# Wireless_FanCoil_Controller_Atmega_v2_2.net
KiCad netlist of a schematic drawn in EAGLE
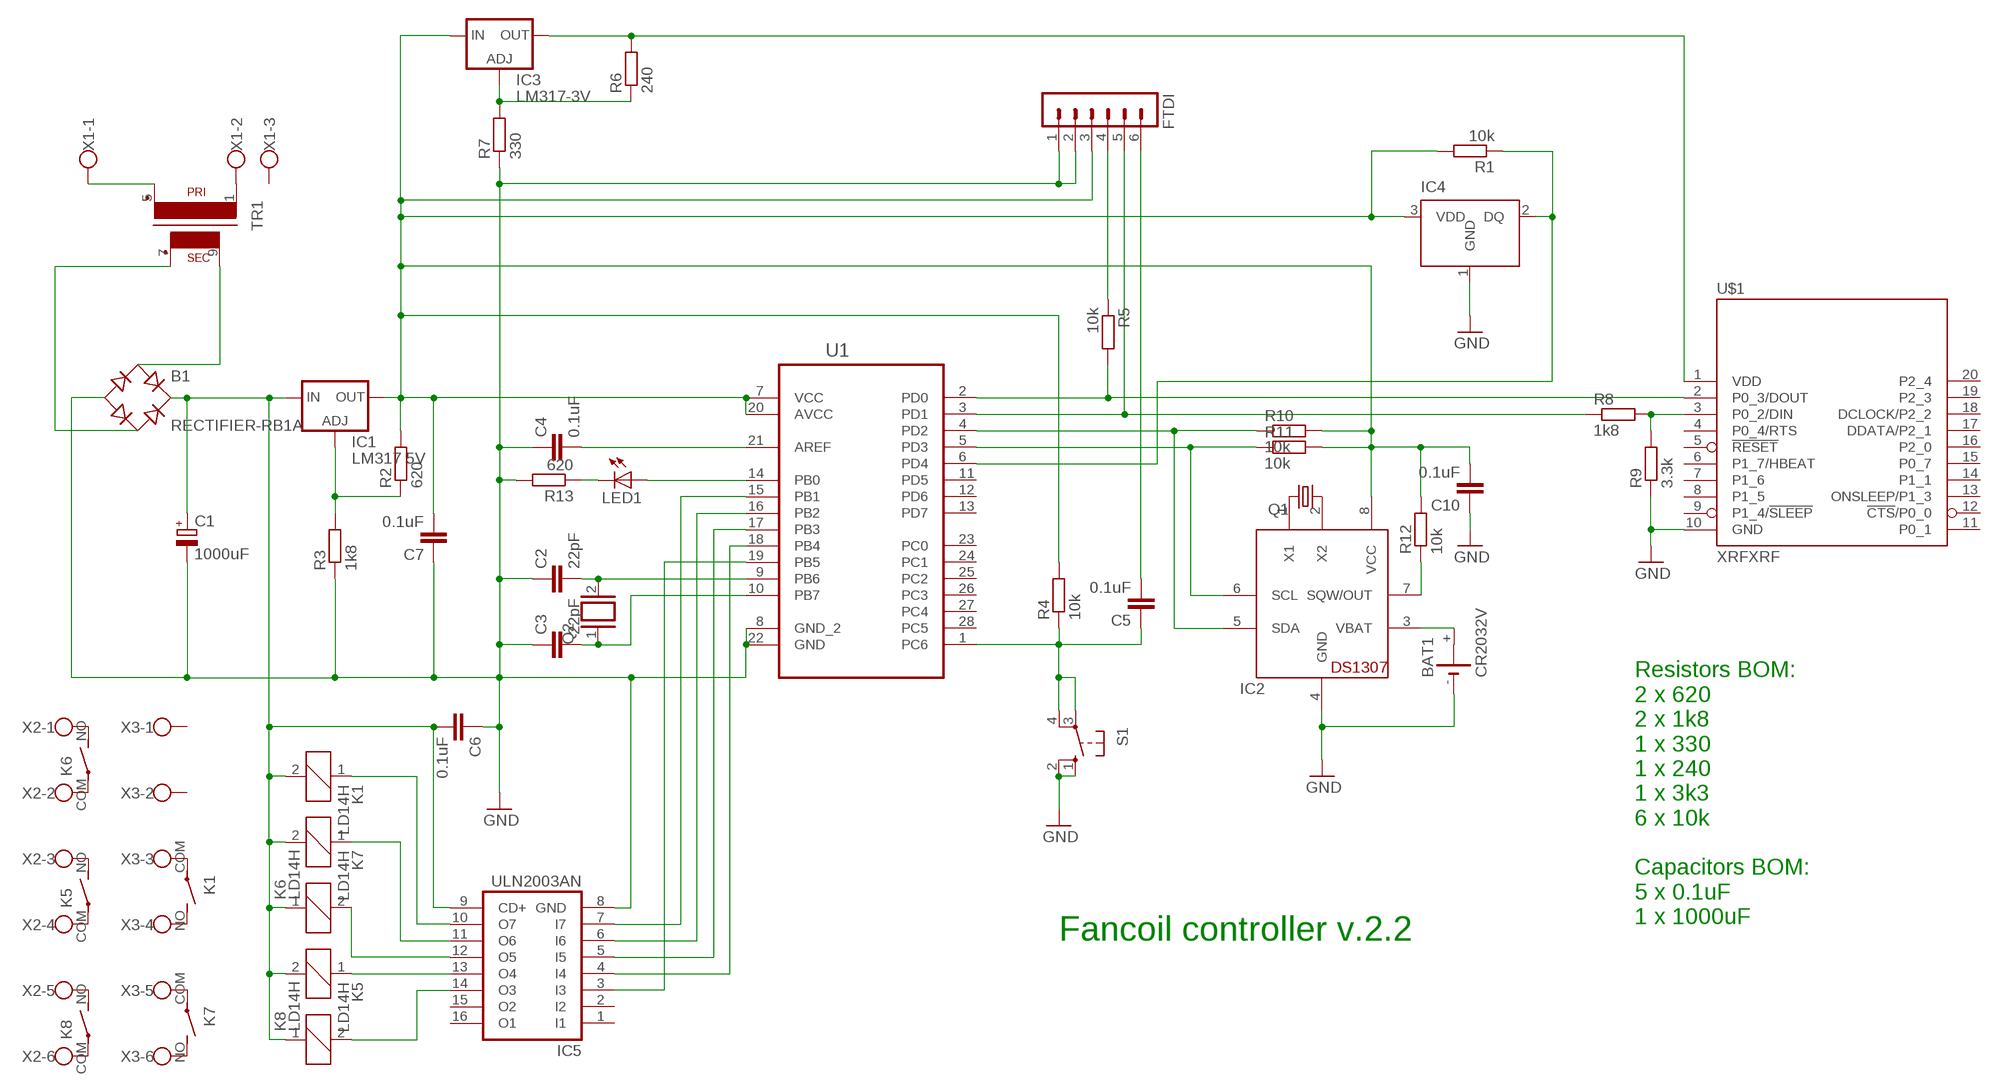
[diagram p0: schematic, sheet 1]

(export (version "E")
  (design (tool "Eeschema 10.0.6"))
  (components
    (comp (ref "B1")
      (value "RECTIFIER-RB1A")
      (footprint "eagle-import:RB1A")
      (libsource (lib "eagle-import") (part "RECTIFIER-RB1A"))
    )
    (comp (ref "BAT1")
      (value "CR2032V")
      (footprint "eagle-import:CR2032V")
      (libsource (lib "eagle-import") (part "CR2032V"))
    )
    (comp (ref "C1")
      (value "1000uF")
      (footprint "eagle-import:E5-10,5")
      (libsource (lib "eagle-import") (part "CPOL-EUE5-10.5"))
    )
    (comp (ref "C2")
      (value "22pF")
      (footprint "eagle-import:C025-025X050")
      (libsource (lib "eagle-import") (part "C-EU025-025X050"))
    )
    (comp (ref "C3")
      (value "22pF")
      (footprint "eagle-import:C025-025X050")
      (libsource (lib "eagle-import") (part "C-EU025-025X050"))
    )
    (comp (ref "C4")
      (value "0.1uF")
      (footprint "eagle-import:C050-025X075")
      (libsource (lib "eagle-import") (part "C-EU050-025X075"))
    )
    (comp (ref "C5")
      (value "0.1uF")
      (footprint "eagle-import:C050-025X075")
      (libsource (lib "eagle-import") (part "C-EU050-025X075"))
    )
    (comp (ref "C6")
      (value "0.1uF")
      (footprint "eagle-import:C050-025X075")
      (libsource (lib "eagle-import") (part "C-EU050-025X075"))
    )
    (comp (ref "C7")
      (value "0.1uF")
      (footprint "eagle-import:C050-025X075")
      (libsource (lib "eagle-import") (part "C-EU050-025X075"))
    )
    (comp (ref "C10")
      (value "0.1uF")
      (footprint "eagle-import:C050-025X075")
      (libsource (lib "eagle-import") (part "C-EU050-025X075"))
    )
    (comp (ref "FTDI")
      (value "MA06-1")
      (footprint "eagle-import:MA06-1")
      (libsource (lib "eagle-import") (part "MA06-1"))
    )
    (comp (ref "IC1")
      (value "LM317 5V")
      (footprint "eagle-import:317TS")
      (libsource (lib "eagle-import") (part "LM317TS"))
    )
    (comp (ref "IC2")
      (value "DS1307")
      (footprint "eagle-import:DIL08")
      (libsource (lib "eagle-import") (part "DS1307"))
    )
    (comp (ref "IC3")
      (value "LM317-3V")
      (footprint "eagle-import:317TS")
      (libsource (lib "eagle-import") (part "LM317TS"))
    )
    (comp (ref "IC4")
      (value "DS1820")
      (footprint "eagle-import:TO-92")
      (libsource (lib "eagle-import") (part "DS1820"))
    )
    (comp (ref "IC5")
      (value "ULN2003AN")
      (footprint "eagle-import:DIL16")
      (libsource (lib "eagle-import") (part "ULN2003AN"))
    )
    (comp (ref "K1")
      (value "LD14H")
      (footprint "eagle-import:LD")
      (fields
        (field (name "MF") "FARNELL")
        (field (name "MPN") "ALD112")
        (field (name "OC_FARNELL") "3727166")
        (field (name "OC_NEWARK") "70C6003")
      )
      (libsource (lib "eagle-import") (part "LD?14H"))
    )
    (comp (ref "K5")
      (value "LD14H")
      (footprint "eagle-import:LD")
      (fields
        (field (name "MF") "FARNELL")
        (field (name "MPN") "ALD112")
        (field (name "OC_FARNELL") "3727166")
        (field (name "OC_NEWARK") "70C6003")
      )
      (libsource (lib "eagle-import") (part "LD?14H"))
    )
    (comp (ref "K6")
      (value "LD14H")
      (footprint "eagle-import:LD")
      (fields
        (field (name "MF") "FARNELL")
        (field (name "MPN") "ALD112")
        (field (name "OC_FARNELL") "3727166")
        (field (name "OC_NEWARK") "70C6003")
      )
      (libsource (lib "eagle-import") (part "LD?14H"))
    )
    (comp (ref "K7")
      (value "LD14H")
      (footprint "eagle-import:LD")
      (fields
        (field (name "MF") "FARNELL")
        (field (name "MPN") "ALD112")
        (field (name "OC_FARNELL") "3727166")
        (field (name "OC_NEWARK") "70C6003")
      )
      (libsource (lib "eagle-import") (part "LD?14H"))
    )
    (comp (ref "K8")
      (value "LD14H")
      (footprint "eagle-import:LD")
      (fields
        (field (name "MF") "FARNELL")
        (field (name "MPN") "ALD112")
        (field (name "OC_FARNELL") "3727166")
        (field (name "OC_NEWARK") "70C6003")
      )
      (libsource (lib "eagle-import") (part "LD?14H"))
    )
    (comp (ref "LED1")
      (value "LED3MM")
      (footprint "eagle-import:LED3MM")
      (libsource (lib "eagle-import") (part "LED3MM"))
    )
    (comp (ref "Q1")
      (value "CRYSTALTC26H")
      (footprint "eagle-import:TC26H")
      (libsource (lib "eagle-import") (part "CRYSTALTC26H"))
    )
    (comp (ref "Q2")
      (value "XTAL/S")
      (footprint "eagle-import:QS")
      (libsource (lib "eagle-import") (part "XTAL/S"))
    )
    (comp (ref "R1")
      (value "10k")
      (footprint "eagle-import:0207_5V")
      (libsource (lib "eagle-import") (part "R-EU_0207/5V"))
    )
    (comp (ref "R2")
      (value "620")
      (footprint "eagle-import:0207_5V")
      (libsource (lib "eagle-import") (part "R-EU_0207/5V"))
    )
    (comp (ref "R3")
      (value "1k8")
      (footprint "eagle-import:0207_5V")
      (libsource (lib "eagle-import") (part "R-EU_0207/5V"))
    )
    (comp (ref "R4")
      (value "10k")
      (footprint "eagle-import:0207_5V")
      (libsource (lib "eagle-import") (part "R-EU_0207/5V"))
    )
    (comp (ref "R5")
      (value "10k")
      (footprint "eagle-import:0207_5V")
      (libsource (lib "eagle-import") (part "R-EU_0207/5V"))
    )
    (comp (ref "R6")
      (value "240")
      (footprint "eagle-import:0207_5V")
      (libsource (lib "eagle-import") (part "R-EU_0207/5V"))
    )
    (comp (ref "R7")
      (value "330")
      (footprint "eagle-import:0207_5V")
      (libsource (lib "eagle-import") (part "R-EU_0207/5V"))
    )
    (comp (ref "R8")
      (value "1k8")
      (footprint "eagle-import:0207_12")
      (libsource (lib "eagle-import") (part "R-EU_0207/12"))
    )
    (comp (ref "R9")
      (value "3.3k")
      (footprint "eagle-import:0207_5V")
      (libsource (lib "eagle-import") (part "R-EU_0207/5V"))
    )
    (comp (ref "R10")
      (value "10k")
      (footprint "eagle-import:0207_5V")
      (libsource (lib "eagle-import") (part "R-EU_0207/5V"))
    )
    (comp (ref "R11")
      (value "10k")
      (footprint "eagle-import:0207_5V")
      (libsource (lib "eagle-import") (part "R-EU_0207/5V"))
    )
    (comp (ref "R12")
      (value "10k")
      (footprint "eagle-import:0207_5V")
      (libsource (lib "eagle-import") (part "R-EU_0207/5V"))
    )
    (comp (ref "R13")
      (value "620")
      (footprint "eagle-import:0207_5V")
      (libsource (lib "eagle-import") (part "R-EU_0207/5V"))
    )
    (comp (ref "S1")
      (value "10-XX")
      (footprint "eagle-import:B3F-10XX")
      (fields (field (name "MPN") "B3F-1000"))
      (libsource (lib "eagle-import") (part "10-XX"))
    )
    (comp (ref "TR1")
      (value "EI30-1")
      (footprint "eagle-import:EI30-1")
      (libsource (lib "eagle-import") (part "EI30-1"))
    )
    (comp (ref "U$1")
      (value "XRFXRF")
      (footprint "eagle-import:XRF")
      (libsource (lib "eagle-import") (part "XRFXRF"))
    )
    (comp (ref "U1")
      (value "ATMEGA328P-PU")
      (footprint "eagle-import:DIP254P762X457-28")
      (libsource (lib "eagle-import") (part "ATMEGA328P-PU"))
    )
    (comp (ref "X1")
      (value "W237-103")
      (footprint "eagle-import:W237-103")
      (fields (field (name "MPN") "237-103"))
      (libsource (lib "eagle-import") (part "W237-103"))
    )
    (comp (ref "X2")
      (value "W237-136")
      (footprint "eagle-import:W237-136")
      (fields (field (name "MPN") "237-136"))
      (libsource (lib "eagle-import") (part "W237-136"))
    )
    (comp (ref "X3")
      (value "W237-136")
      (footprint "eagle-import:W237-136")
      (fields (field (name "MPN") "237-136"))
      (libsource (lib "eagle-import") (part "W237-136"))
    )
  )
  (nets
    (net (code "1") (name "GND") (class "Default")
      (node (ref "B1") (pin "-") (pinfunction "-_-") (pintype "passive"))
      (node (ref "BAT1") (pin "-") (pinfunction "-_-") (pintype "passive"))
      (node (ref "C1") (pin "-") (pinfunction "-_-") (pintype "passive"))
      (node (ref "C10") (pin "1") (pinfunction "1_1") (pintype "passive"))
      (node (ref "C2") (pin "1") (pinfunction "1_1") (pintype "passive"))
      (node (ref "C3") (pin "1") (pinfunction "1_1") (pintype "passive"))
      (node (ref "C4") (pin "1") (pinfunction "1_1") (pintype "passive"))
      (node (ref "C6") (pin "1") (pinfunction "1_1") (pintype "passive"))
      (node (ref "C7") (pin "1") (pinfunction "1_1") (pintype "passive"))
      (node (ref "FTDI") (pin "1") (pinfunction "1_1") (pintype "passive"))
      (node (ref "FTDI") (pin "2") (pinfunction "2_2") (pintype "passive"))
      (node (ref "IC2") (pin "4") (pinfunction "GND_4") (pintype "power_in"))
      (node (ref "IC4") (pin "1") (pinfunction "GND_1") (pintype "power_in"))
      (node (ref "IC5") (pin "8") (pinfunction "GND_8") (pintype "power_in"))
      (node (ref "R13") (pin "2") (pinfunction "2_2") (pintype "passive"))
      (node (ref "R3") (pin "1") (pinfunction "1_1") (pintype "passive"))
      (node (ref "R7") (pin "1") (pinfunction "1_1") (pintype "passive"))
      (node (ref "R9") (pin "1") (pinfunction "1_1") (pintype "passive"))
      (node (ref "S1") (pin "1") (pinfunction "S_1") (pintype "passive"))
      (node (ref "S1") (pin "2") (pinfunction "S1_2") (pintype "passive"))
      (node (ref "U$1") (pin "10") (pinfunction "GND_10") (pintype "power_in"))
      (node (ref "U1") (pin "22") (pinfunction "GND_22") (pintype "passive"))
      (node (ref "U1") (pin "8") (pinfunction "GND_2_8") (pintype "passive"))
    )
    (net (code "2") (name "Net-(C5-Pad2)") (class "Default")
      (node (ref "C5") (pin "2") (pinfunction "2_2") (pintype "passive"))
      (node (ref "FTDI") (pin "6") (pinfunction "6_6") (pintype "passive"))
    )
    (net (code "3") (name "Net-(FTDI-Pad4)") (class "Default")
      (node (ref "FTDI") (pin "4") (pinfunction "4_4") (pintype "passive"))
      (node (ref "R5") (pin "1") (pinfunction "1_1") (pintype "passive"))
    )
    (net (code "4") (name "Net-(IC1-ADJ)") (class "Default")
      (node (ref "IC1") (pin "1") (pinfunction "ADJ_1") (pintype "input"))
      (node (ref "R2") (pin "1") (pinfunction "1_1") (pintype "passive"))
      (node (ref "R3") (pin "2") (pinfunction "2_2") (pintype "passive"))
    )
    (net (code "5") (name "Net-(IC1-IN)") (class "Default")
      (node (ref "B1") (pin "+") (pinfunction "+_+") (pintype "passive"))
      (node (ref "C1") (pin "+") (pinfunction "+_+") (pintype "passive"))
      (node (ref "C6") (pin "2") (pinfunction "2_2") (pintype "passive"))
      (node (ref "IC1") (pin "3") (pinfunction "IN_3") (pintype "input"))
      (node (ref "IC5") (pin "9") (pinfunction "CD+_9") (pintype "passive"))
      (node (ref "K1") (pin "2") (pinfunction "2_2") (pintype "passive"))
      (node (ref "K5") (pin "2") (pinfunction "2_2") (pintype "passive"))
      (node (ref "K6") (pin "1") (pinfunction "1_1") (pintype "passive"))
      (node (ref "K7") (pin "2") (pinfunction "2_2") (pintype "passive"))
      (node (ref "K8") (pin "1") (pinfunction "1_1") (pintype "passive"))
    )
    (net (code "6") (name "Net-(IC1-OUT)") (class "Default")
      (node (ref "C10") (pin "2") (pinfunction "2_2") (pintype "passive"))
      (node (ref "C7") (pin "2") (pinfunction "2_2") (pintype "passive"))
      (node (ref "FTDI") (pin "3") (pinfunction "3_3") (pintype "passive"))
      (node (ref "IC1") (pin "2") (pinfunction "OUT_2") (pintype "passive"))
      (node (ref "IC2") (pin "8") (pinfunction "VCC_8") (pintype "power_in"))
      (node (ref "IC3") (pin "3") (pinfunction "IN_3") (pintype "input"))
      (node (ref "IC4") (pin "3") (pinfunction "VDD_3") (pintype "input"))
      (node (ref "R1") (pin "2") (pinfunction "2_2") (pintype "passive"))
      (node (ref "R10") (pin "2") (pinfunction "2_2") (pintype "passive"))
      (node (ref "R11") (pin "2") (pinfunction "2_2") (pintype "passive"))
      (node (ref "R12") (pin "2") (pinfunction "2_2") (pintype "passive"))
      (node (ref "R2") (pin "2") (pinfunction "2_2") (pintype "passive"))
      (node (ref "R4") (pin "2") (pinfunction "2_2") (pintype "passive"))
      (node (ref "U1") (pin "20") (pinfunction "AVCC_20") (pintype "power_in"))
      (node (ref "U1") (pin "7") (pinfunction "VCC_7") (pintype "power_in"))
    )
    (net (code "7") (name "Net-(IC2-SCL)") (class "Default")
      (node (ref "IC2") (pin "6") (pinfunction "SCL_6") (pintype "bidirectional"))
      (node (ref "R11") (pin "1") (pinfunction "1_1") (pintype "passive"))
      (node (ref "U1") (pin "5") (pinfunction "PD3_5") (pintype "bidirectional"))
    )
    (net (code "8") (name "Net-(IC2-SDA)") (class "Default")
      (node (ref "IC2") (pin "5") (pinfunction "SDA_5") (pintype "bidirectional"))
      (node (ref "R10") (pin "1") (pinfunction "1_1") (pintype "passive"))
      (node (ref "U1") (pin "4") (pinfunction "PD2_4") (pintype "bidirectional"))
    )
    (net (code "9") (name "Net-(IC2-SQW{slash}OUT)") (class "Default")
      (node (ref "IC2") (pin "7") (pinfunction "SQW/OUT_7") (pintype "bidirectional"))
      (node (ref "R12") (pin "1") (pinfunction "1_1") (pintype "passive"))
    )
    (net (code "10") (name "Net-(IC2-VBAT)") (class "Default")
      (node (ref "BAT1") (pin "+") (pinfunction "+_+") (pintype "passive"))
      (node (ref "IC2") (pin "3") (pinfunction "VBAT_3") (pintype "power_in"))
    )
    (net (code "11") (name "Net-(IC2-X1)") (class "Default")
      (node (ref "IC2") (pin "1") (pinfunction "X1_1") (pintype "passive"))
      (node (ref "Q1") (pin "2") (pinfunction "2_2") (pintype "passive"))
    )
    (net (code "12") (name "Net-(IC2-X2)") (class "Default")
      (node (ref "IC2") (pin "2") (pinfunction "X2_2") (pintype "passive"))
      (node (ref "Q1") (pin "1") (pinfunction "1_1") (pintype "passive"))
    )
    (net (code "13") (name "Net-(IC3-ADJ)") (class "Default")
      (node (ref "IC3") (pin "1") (pinfunction "ADJ_1") (pintype "input"))
      (node (ref "R6") (pin "1") (pinfunction "1_1") (pintype "passive"))
      (node (ref "R7") (pin "2") (pinfunction "2_2") (pintype "passive"))
    )
    (net (code "14") (name "Net-(IC3-OUT)") (class "Default")
      (node (ref "IC3") (pin "2") (pinfunction "OUT_2") (pintype "passive"))
      (node (ref "R6") (pin "2") (pinfunction "2_2") (pintype "passive"))
      (node (ref "U$1") (pin "1") (pinfunction "VDD_1") (pintype "power_in"))
    )
    (net (code "15") (name "Net-(IC4-DQ)") (class "Default")
      (node (ref "IC4") (pin "2") (pinfunction "DQ_2") (pintype "output"))
      (node (ref "R1") (pin "1") (pinfunction "1_1") (pintype "passive"))
      (node (ref "U1") (pin "6") (pinfunction "PD4_6") (pintype "bidirectional"))
    )
    (net (code "16") (name "Net-(IC5-I3)") (class "Default")
      (node (ref "IC5") (pin "3") (pinfunction "I3_3") (pintype "input"))
      (node (ref "U1") (pin "19") (pinfunction "PB5_19") (pintype "bidirectional"))
    )
    (net (code "17") (name "Net-(IC5-I4)") (class "Default")
      (node (ref "IC5") (pin "4") (pinfunction "I4_4") (pintype "input"))
      (node (ref "U1") (pin "18") (pinfunction "PB4_18") (pintype "bidirectional"))
    )
    (net (code "18") (name "Net-(IC5-I5)") (class "Default")
      (node (ref "IC5") (pin "5") (pinfunction "I5_5") (pintype "input"))
      (node (ref "U1") (pin "17") (pinfunction "PB3_17") (pintype "bidirectional"))
    )
    (net (code "19") (name "Net-(IC5-I6)") (class "Default")
      (node (ref "IC5") (pin "6") (pinfunction "I6_6") (pintype "input"))
      (node (ref "U1") (pin "16") (pinfunction "PB2_16") (pintype "bidirectional"))
    )
    (net (code "20") (name "Net-(IC5-I7)") (class "Default")
      (node (ref "IC5") (pin "7") (pinfunction "I7_7") (pintype "input"))
      (node (ref "U1") (pin "15") (pinfunction "PB1_15") (pintype "bidirectional"))
    )
    (net (code "21") (name "Net-(IC5-O3)") (class "Default")
      (node (ref "IC5") (pin "14") (pinfunction "O3_14") (pintype "open_collector"))
      (node (ref "K8") (pin "2") (pinfunction "2_2") (pintype "passive"))
    )
    (net (code "22") (name "Net-(IC5-O4)") (class "Default")
      (node (ref "IC5") (pin "13") (pinfunction "O4_13") (pintype "open_collector"))
      (node (ref "K5") (pin "1") (pinfunction "1_1") (pintype "passive"))
    )
    (net (code "23") (name "Net-(IC5-O5)") (class "Default")
      (node (ref "IC5") (pin "12") (pinfunction "O5_12") (pintype "open_collector"))
      (node (ref "K6") (pin "2") (pinfunction "2_2") (pintype "passive"))
    )
    (net (code "24") (name "Net-(IC5-O6)") (class "Default")
      (node (ref "IC5") (pin "11") (pinfunction "O6_11") (pintype "open_collector"))
      (node (ref "K7") (pin "1") (pinfunction "1_1") (pintype "passive"))
    )
    (net (code "25") (name "Net-(IC5-O7)") (class "Default")
      (node (ref "IC5") (pin "10") (pinfunction "O7_10") (pintype "open_collector"))
      (node (ref "K1") (pin "1") (pinfunction "1_1") (pintype "passive"))
    )
    (net (code "26") (name "Net-(K1B-P)") (class "Default")
      (node (ref "K1") (pin "COM") (pinfunction "P_COM") (pintype "passive"))
      (node (ref "X3") (pin "3") (pinfunction "KL_3") (pintype "passive"))
    )
    (net (code "27") (name "Net-(K1B-S)") (class "Default")
      (node (ref "K1") (pin "NO") (pinfunction "S_NO") (pintype "passive"))
      (node (ref "X3") (pin "4") (pinfunction "KL_4") (pintype "passive"))
    )
    (net (code "28") (name "Net-(K5B-P)") (class "Default")
      (node (ref "K5") (pin "COM") (pinfunction "P_COM") (pintype "passive"))
      (node (ref "X2") (pin "4") (pinfunction "KL_4") (pintype "passive"))
    )
    (net (code "29") (name "Net-(K5B-S)") (class "Default")
      (node (ref "K5") (pin "NO") (pinfunction "S_NO") (pintype "passive"))
      (node (ref "X2") (pin "3") (pinfunction "KL_3") (pintype "passive"))
    )
    (net (code "30") (name "Net-(K6B-P)") (class "Default")
      (node (ref "K6") (pin "COM") (pinfunction "P_COM") (pintype "passive"))
      (node (ref "X2") (pin "2") (pinfunction "KL_2") (pintype "passive"))
    )
    (net (code "31") (name "Net-(K6B-S)") (class "Default")
      (node (ref "K6") (pin "NO") (pinfunction "S_NO") (pintype "passive"))
      (node (ref "X2") (pin "1") (pinfunction "KL_1") (pintype "passive"))
    )
    (net (code "32") (name "Net-(K7B-P)") (class "Default")
      (node (ref "K7") (pin "COM") (pinfunction "P_COM") (pintype "passive"))
      (node (ref "X3") (pin "5") (pinfunction "KL_5") (pintype "passive"))
    )
    (net (code "33") (name "Net-(K7B-S)") (class "Default")
      (node (ref "K7") (pin "NO") (pinfunction "S_NO") (pintype "passive"))
      (node (ref "X3") (pin "6") (pinfunction "KL_6") (pintype "passive"))
    )
    (net (code "34") (name "Net-(K8B-P)") (class "Default")
      (node (ref "K8") (pin "COM") (pinfunction "P_COM") (pintype "passive"))
      (node (ref "X2") (pin "6") (pinfunction "KL_6") (pintype "passive"))
    )
    (net (code "35") (name "Net-(K8B-S)") (class "Default")
      (node (ref "K8") (pin "NO") (pinfunction "S_NO") (pintype "passive"))
      (node (ref "X2") (pin "5") (pinfunction "KL_5") (pintype "passive"))
    )
    (net (code "36") (name "Net-(LED1-C)") (class "Default")
      (node (ref "LED1") (pin "K") (pinfunction "C_K") (pintype "passive"))
      (node (ref "R13") (pin "1") (pinfunction "1_1") (pintype "passive"))
    )
    (net (code "37") (name "Net-(S1-P)") (class "Default")
      (node (ref "C5") (pin "1") (pinfunction "1_1") (pintype "passive"))
      (node (ref "R4") (pin "1") (pinfunction "1_1") (pintype "passive"))
      (node (ref "S1") (pin "3") (pinfunction "P_3") (pintype "passive"))
      (node (ref "S1") (pin "4") (pinfunction "P1_4") (pintype "passive"))
      (node (ref "U1") (pin "1") (pinfunction "PC6_1") (pintype "bidirectional"))
    )
    (net (code "38") (name "Net-(TR1-P1)") (class "Default")
      (node (ref "TR1") (pin "1") (pinfunction "P1_1") (pintype "passive"))
      (node (ref "X1") (pin "2") (pinfunction "KL_2") (pintype "passive"))
    )
    (net (code "39") (name "Net-(TR1-P2)") (class "Default")
      (node (ref "TR1") (pin "5") (pinfunction "P2_5") (pintype "passive"))
      (node (ref "X1") (pin "1") (pinfunction "KL_1") (pintype "passive"))
    )
    (net (code "40") (name "Net-(TR1-S3)") (class "Default")
      (node (ref "B1") (pin "AC2") (pinfunction "AC2_AC2") (pintype "passive"))
      (node (ref "TR1") (pin "7") (pinfunction "S3_7") (pintype "passive"))
    )
    (net (code "41") (name "Net-(TR1-S4)") (class "Default")
      (node (ref "B1") (pin "AC1") (pinfunction "AC1_AC1") (pintype "passive"))
      (node (ref "TR1") (pin "9") (pinfunction "S4_9") (pintype "passive"))
    )
    (net (code "42") (name "Net-(U$1-P0_2{slash}DIN)") (class "Default")
      (node (ref "R8") (pin "2") (pinfunction "2_2") (pintype "passive"))
      (node (ref "R9") (pin "2") (pinfunction "2_2") (pintype "passive"))
      (node (ref "U$1") (pin "3") (pinfunction "P0_2/DIN_3") (pintype "input"))
    )
    (net (code "43") (name "Net-(U$1-P0_3{slash}DOUT)") (class "Default")
      (node (ref "R5") (pin "2") (pinfunction "2_2") (pintype "passive"))
      (node (ref "U$1") (pin "2") (pinfunction "P0_3/DOUT_2") (pintype "output"))
      (node (ref "U1") (pin "2") (pinfunction "PD0_2") (pintype "bidirectional"))
    )
    (net (code "44") (name "Net-(U1-AREF)") (class "Default")
      (node (ref "C4") (pin "2") (pinfunction "2_2") (pintype "passive"))
      (node (ref "U1") (pin "21") (pinfunction "AREF_21") (pintype "input"))
    )
    (net (code "45") (name "Net-(U1-PB0)") (class "Default")
      (node (ref "LED1") (pin "A") (pinfunction "A_A") (pintype "passive"))
      (node (ref "U1") (pin "14") (pinfunction "PB0_14") (pintype "bidirectional"))
    )
    (net (code "46") (name "Net-(U1-PB6)") (class "Default")
      (node (ref "C2") (pin "2") (pinfunction "2_2") (pintype "passive"))
      (node (ref "Q2") (pin "2") (pinfunction "2_2") (pintype "passive"))
      (node (ref "U1") (pin "9") (pinfunction "PB6_9") (pintype "bidirectional"))
    )
    (net (code "47") (name "Net-(U1-PB7)") (class "Default")
      (node (ref "C3") (pin "2") (pinfunction "2_2") (pintype "passive"))
      (node (ref "Q2") (pin "1") (pinfunction "1_1") (pintype "passive"))
      (node (ref "U1") (pin "10") (pinfunction "PB7_10") (pintype "bidirectional"))
    )
    (net (code "48") (name "Net-(U1-PD1)") (class "Default")
      (node (ref "FTDI") (pin "5") (pinfunction "5_5") (pintype "passive"))
      (node (ref "R8") (pin "1") (pinfunction "1_1") (pintype "passive"))
      (node (ref "U1") (pin "3") (pinfunction "PD1_3") (pintype "bidirectional"))
    )
    (net (code "49") (name "unconnected-(BAT1-+-Pad+@1)") (class "Default")
      (node (ref "BAT1") (pin "+@1") (pinfunction "+_+@1") (pintype "passive"))
    )
    (net (code "50") (name "unconnected-(IC5-I1-Pad1)") (class "Default")
      (node (ref "IC5") (pin "1") (pinfunction "I1_1") (pintype "input"))
    )
    (net (code "51") (name "unconnected-(IC5-I2-Pad2)") (class "Default")
      (node (ref "IC5") (pin "2") (pinfunction "I2_2") (pintype "input"))
    )
    (net (code "52") (name "unconnected-(IC5-O1-Pad16)") (class "Default")
      (node (ref "IC5") (pin "16") (pinfunction "O1_16") (pintype "open_collector"))
    )
    (net (code "53") (name "unconnected-(IC5-O2-Pad15)") (class "Default")
      (node (ref "IC5") (pin "15") (pinfunction "O2_15") (pintype "open_collector"))
    )
    (net (code "54") (name "unconnected-(U$1-DCLOCK{slash}P2_2-Pad18)") (class "Default")
      (node (ref "U$1") (pin "18") (pinfunction "DCLOCK/P2_2_18") (pintype "bidirectional"))
    )
    (net (code "55") (name "unconnected-(U$1-DDATA{slash}P2_1-Pad17)") (class "Default")
      (node (ref "U$1") (pin "17") (pinfunction "DDATA/P2_1_17") (pintype "bidirectional"))
    )
    (net (code "56") (name "unconnected-(U$1-ONSLEEP{slash}P1_3-Pad13)") (class "Default")
      (node (ref "U$1") (pin "13") (pinfunction "ONSLEEP/P1_3_13") (pintype "bidirectional"))
    )
    (net (code "57") (name "unconnected-(U$1-P0_1-Pad11)") (class "Default")
      (node (ref "U$1") (pin "11") (pinfunction "P0_1_11") (pintype "bidirectional"))
    )
    (net (code "58") (name "unconnected-(U$1-P0_4{slash}RTS-Pad4)") (class "Default")
      (node (ref "U$1") (pin "4") (pinfunction "P0_4/RTS_4") (pintype "bidirectional"))
    )
    (net (code "59") (name "unconnected-(U$1-P0_7-Pad15)") (class "Default")
      (node (ref "U$1") (pin "15") (pinfunction "P0_7_15") (pintype "bidirectional"))
    )
    (net (code "60") (name "unconnected-(U$1-P1_1-Pad14)") (class "Default")
      (node (ref "U$1") (pin "14") (pinfunction "P1_1_14") (pintype "bidirectional"))
    )
    (net (code "61") (name "unconnected-(U$1-P1_4{slash}~{SLEEP}-Pad9)") (class "Default")
      (node (ref "U$1") (pin "9") (pinfunction "P1_4/~{SLEEP}_9") (pintype "bidirectional"))
    )
    (net (code "62") (name "unconnected-(U$1-P1_5-Pad8)") (class "Default")
      (node (ref "U$1") (pin "8") (pinfunction "P1_5_8") (pintype "bidirectional"))
    )
    (net (code "63") (name "unconnected-(U$1-P1_6-Pad7)") (class "Default")
      (node (ref "U$1") (pin "7") (pinfunction "P1_6_7") (pintype "bidirectional"))
    )
    (net (code "64") (name "unconnected-(U$1-P1_7{slash}HBEAT-Pad6)") (class "Default")
      (node (ref "U$1") (pin "6") (pinfunction "P1_7/HBEAT_6") (pintype "bidirectional"))
    )
    (net (code "65") (name "unconnected-(U$1-P2_0-Pad16)") (class "Default")
      (node (ref "U$1") (pin "16") (pinfunction "P2_0_16") (pintype "input"))
    )
    (net (code "66") (name "unconnected-(U$1-P2_3-Pad19)") (class "Default")
      (node (ref "U$1") (pin "19") (pinfunction "P2_3_19") (pintype "bidirectional"))
    )
    (net (code "67") (name "unconnected-(U$1-P2_4-Pad20)") (class "Default")
      (node (ref "U$1") (pin "20") (pinfunction "P2_4_20") (pintype "bidirectional"))
    )
    (net (code "68") (name "unconnected-(U$1-~{CTS}{slash}P0_0-Pad12)") (class "Default")
      (node (ref "U$1") (pin "12") (pinfunction "~{CTS}/P0_0_12") (pintype "output"))
    )
    (net (code "69") (name "unconnected-(U$1-~{RESET}-Pad5)") (class "Default")
      (node (ref "U$1") (pin "5") (pinfunction "~{RESET}_5") (pintype "input"))
    )
    (net (code "70") (name "unconnected-(U1-PC0-Pad23)") (class "Default")
      (node (ref "U1") (pin "23") (pinfunction "PC0_23") (pintype "bidirectional"))
    )
    (net (code "71") (name "unconnected-(U1-PC1-Pad24)") (class "Default")
      (node (ref "U1") (pin "24") (pinfunction "PC1_24") (pintype "bidirectional"))
    )
    (net (code "72") (name "unconnected-(U1-PC2-Pad25)") (class "Default")
      (node (ref "U1") (pin "25") (pinfunction "PC2_25") (pintype "bidirectional"))
    )
    (net (code "73") (name "unconnected-(U1-PC3-Pad26)") (class "Default")
      (node (ref "U1") (pin "26") (pinfunction "PC3_26") (pintype "bidirectional"))
    )
    (net (code "74") (name "unconnected-(U1-PC4-Pad27)") (class "Default")
      (node (ref "U1") (pin "27") (pinfunction "PC4_27") (pintype "bidirectional"))
    )
    (net (code "75") (name "unconnected-(U1-PC5-Pad28)") (class "Default")
      (node (ref "U1") (pin "28") (pinfunction "PC5_28") (pintype "bidirectional"))
    )
    (net (code "76") (name "unconnected-(U1-PD5-Pad11)") (class "Default")
      (node (ref "U1") (pin "11") (pinfunction "PD5_11") (pintype "bidirectional"))
    )
    (net (code "77") (name "unconnected-(U1-PD6-Pad12)") (class "Default")
      (node (ref "U1") (pin "12") (pinfunction "PD6_12") (pintype "bidirectional"))
    )
    (net (code "78") (name "unconnected-(U1-PD7-Pad13)") (class "Default")
      (node (ref "U1") (pin "13") (pinfunction "PD7_13") (pintype "bidirectional"))
    )
    (net (code "79") (name "unconnected-(X1C-KL-Pad3)") (class "Default")
      (node (ref "X1") (pin "3") (pinfunction "KL_3") (pintype "passive"))
    )
    (net (code "80") (name "unconnected-(X3A-KL-Pad1)") (class "Default")
      (node (ref "X3") (pin "1") (pinfunction "KL_1") (pintype "passive"))
    )
    (net (code "81") (name "unconnected-(X3B-KL-Pad2)") (class "Default")
      (node (ref "X3") (pin "2") (pinfunction "KL_2") (pintype "passive"))
    )
  )
)
